# MAX4995C_-_Programmable_Current-Limit_Sw.net
KiCad netlist of a schematic drawn in EAGLE
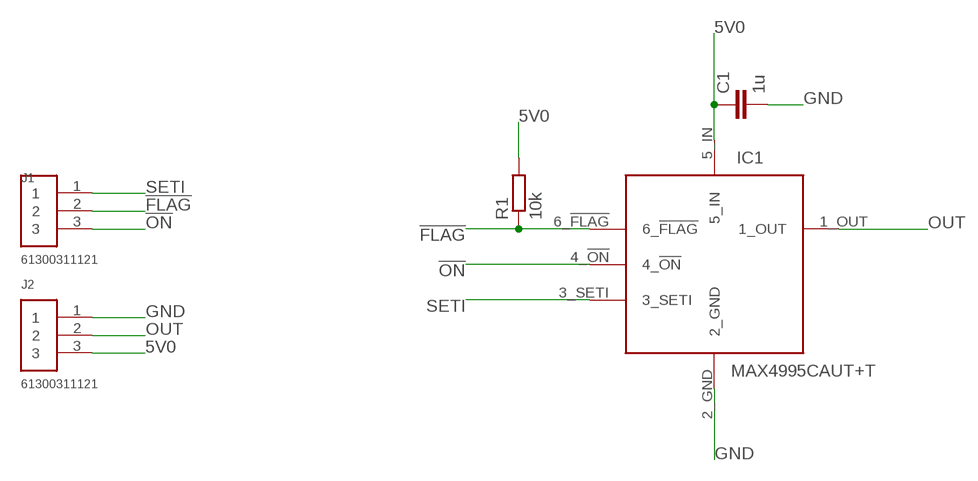
[diagram p0: schematic, sheet 1]

(export (version "E")
  (design (tool "Eeschema 10.0.6"))
  (components
    (comp (ref "C1")
      (value "1u")
      (footprint "eagle-import:C0805")
      (libsource (lib "eagle-import") (part "C-EUC0805"))
    )
    (comp (ref "IC1")
      (value "MAX4995CAUT+T")
      (footprint "eagle-import:SOT23-6")
      (libsource (lib "eagle-import") (part "MAX4995C"))
    )
    (comp (ref "J1")
      (value "61300311121")
      (footprint "eagle-import:61300311121")
      (fields
        (field (name "DIGI_KEY_PART_NUMBER") "732-5316-ND")
        (field (name "MANUFACTURER") "Wurth Electronics Inc.")
        (field (name "CREATED_BY") "PCBLayout.com")
      )
      (libsource (lib "eagle-import") (part "61300311121"))
    )
    (comp (ref "J2")
      (value "61300311121")
      (footprint "eagle-import:61300311121")
      (fields
        (field (name "DIGI_KEY_PART_NUMBER") "732-5316-ND")
        (field (name "MANUFACTURER") "Wurth Electronics Inc.")
        (field (name "CREATED_BY") "PCBLayout.com")
      )
      (libsource (lib "eagle-import") (part "61300311121"))
    )
    (comp (ref "R1")
      (value "10k")
      (footprint "eagle-import:R0805")
      (libsource (lib "eagle-import") (part "R-EU_R0805"))
    )
  )
  (nets
    (net (code "1") (name "/5V0") (class "Default")
      (node (ref "C1") (pin "1") (pinfunction "1_1") (pintype "passive"))
      (node (ref "IC1") (pin "5_IN") (pinfunction "5_IN_5_IN") (pintype "bidirectional"))
      (node (ref "J2") (pin "3") (pinfunction "3_3") (pintype "passive"))
      (node (ref "R1") (pin "2") (pinfunction "2_2") (pintype "passive"))
    )
    (net (code "2") (name "/GND") (class "Default")
      (node (ref "C1") (pin "2") (pinfunction "2_2") (pintype "passive"))
      (node (ref "IC1") (pin "2_GND") (pinfunction "2_GND_2_GND") (pintype "bidirectional"))
      (node (ref "J2") (pin "1") (pinfunction "1_1") (pintype "passive"))
    )
    (net (code "3") (name "/OUT") (class "Default")
      (node (ref "IC1") (pin "1_OUT") (pinfunction "1_OUT_1_OUT") (pintype "bidirectional"))
      (node (ref "J2") (pin "2") (pinfunction "2_2") (pintype "passive"))
    )
    (net (code "4") (name "/SETI") (class "Default")
      (node (ref "IC1") (pin "3_SETI") (pinfunction "3_SETI_3_SETI") (pintype "bidirectional"))
      (node (ref "J1") (pin "1") (pinfunction "1_1") (pintype "passive"))
    )
    (net (code "5") (name "/~{FLAG}") (class "Default")
      (node (ref "IC1") (pin "6_!FLAG!") (pinfunction "6_~{FLAG}_6_!FLAG!") (pintype "bidirectional"))
      (node (ref "J1") (pin "2") (pinfunction "2_2") (pintype "passive"))
      (node (ref "R1") (pin "1") (pinfunction "1_1") (pintype "passive"))
    )
    (net (code "6") (name "/~{ON}") (class "Default")
      (node (ref "IC1") (pin "4_!ON!") (pinfunction "4_~{ON}_4_!ON!") (pintype "bidirectional"))
      (node (ref "J1") (pin "3") (pinfunction "3_3") (pintype "passive"))
    )
  )
)
